# W990X.net
KiCad netlist of a schematic drawn in EAGLE
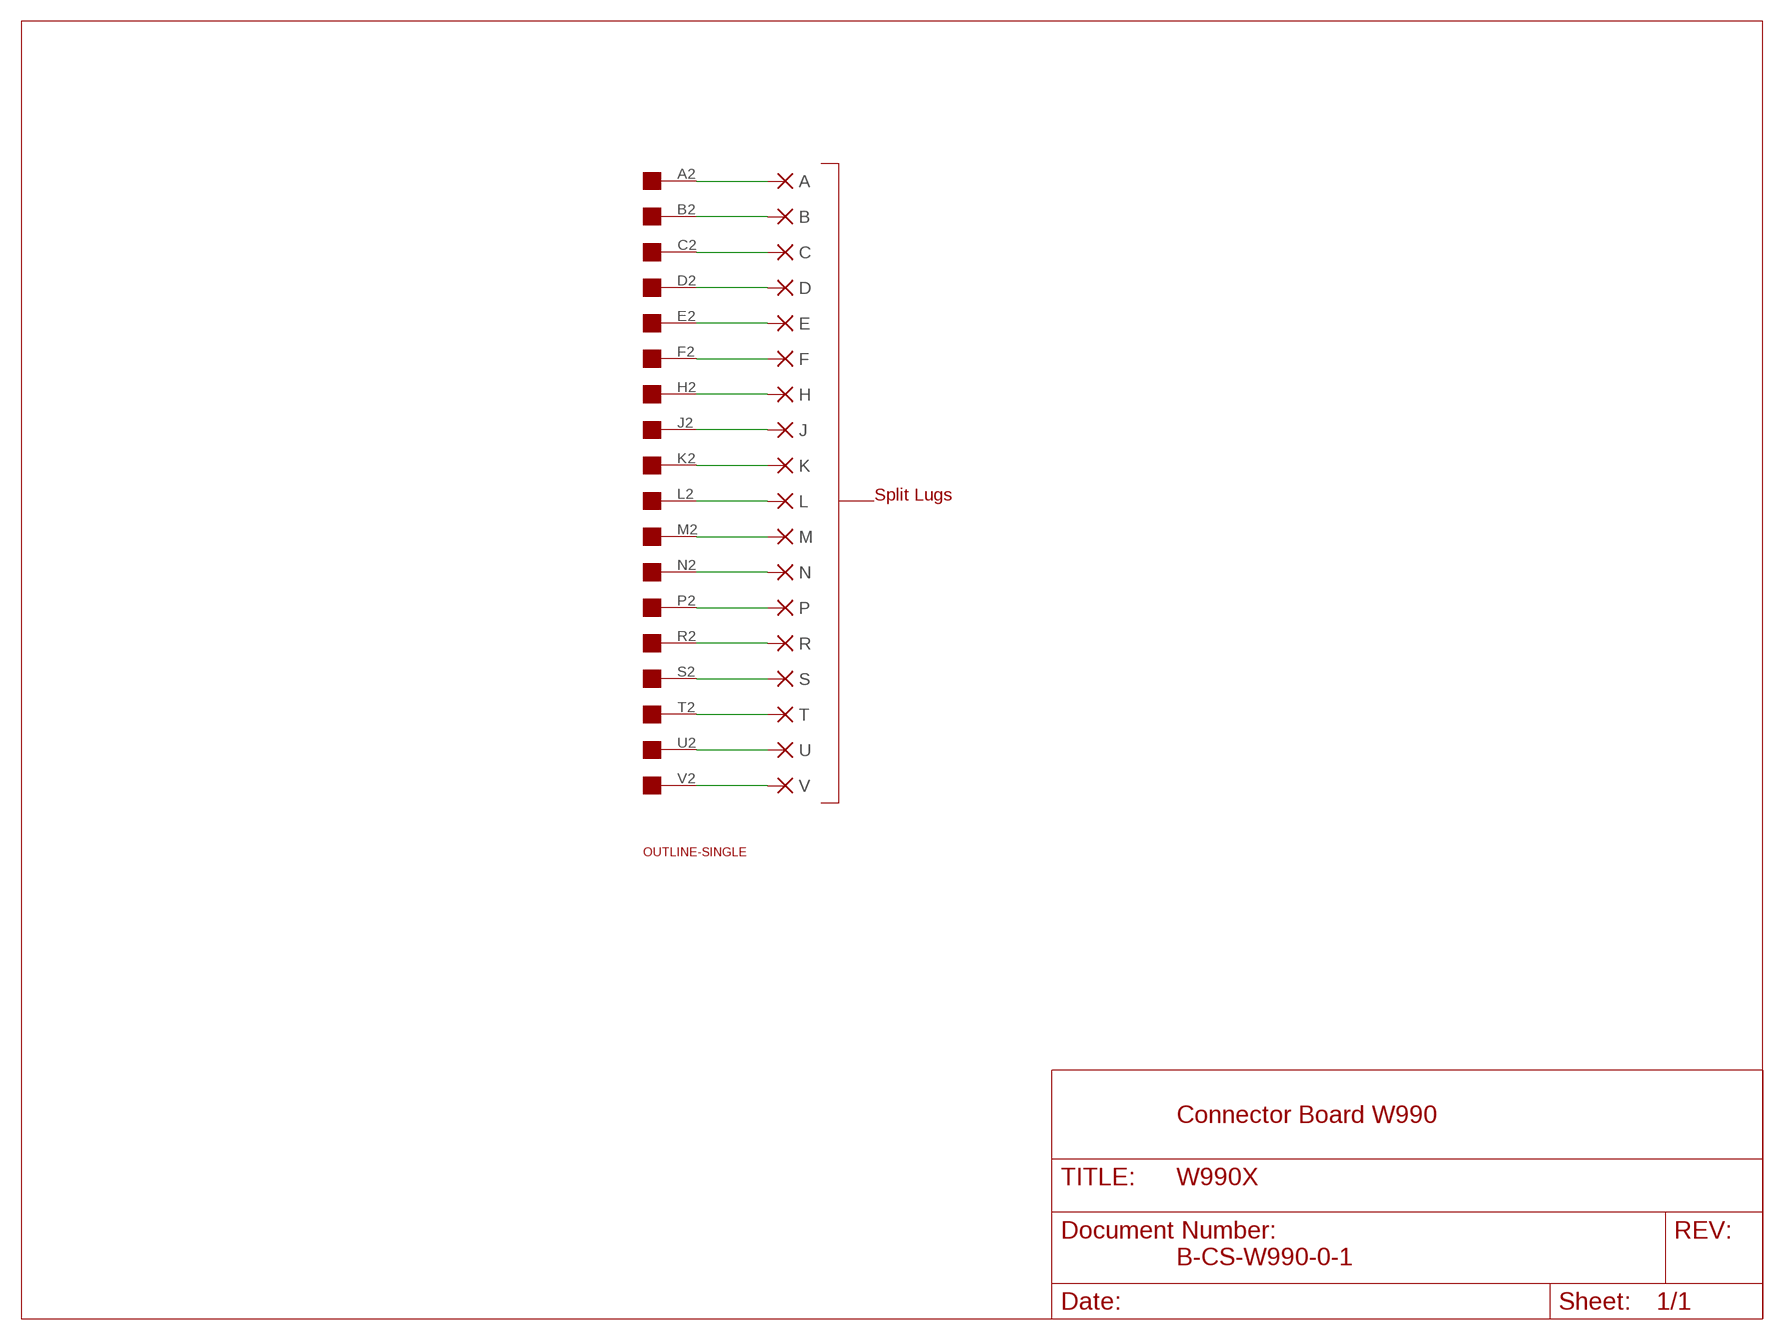
[diagram p0: schematic, sheet 1]

(export (version "E")
  (design (tool "Eeschema 10.0.6"))
  (components
    (comp (ref "A")
      (value "PAD-0465")
      (footprint "eagle-import:0465")
      (libsource (lib "eagle-import") (part "PAD-0465"))
    )
    (comp (ref "B")
      (value "PAD-0465")
      (footprint "eagle-import:0465")
      (libsource (lib "eagle-import") (part "PAD-0465"))
    )
    (comp (ref "C")
      (value "PAD-0465")
      (footprint "eagle-import:0465")
      (libsource (lib "eagle-import") (part "PAD-0465"))
    )
    (comp (ref "D")
      (value "PAD-0465")
      (footprint "eagle-import:0465")
      (libsource (lib "eagle-import") (part "PAD-0465"))
    )
    (comp (ref "E")
      (value "PAD-0465")
      (footprint "eagle-import:0465")
      (libsource (lib "eagle-import") (part "PAD-0465"))
    )
    (comp (ref "F")
      (value "PAD-0465")
      (footprint "eagle-import:0465")
      (libsource (lib "eagle-import") (part "PAD-0465"))
    )
    (comp (ref "H")
      (value "PAD-0465")
      (footprint "eagle-import:0465")
      (libsource (lib "eagle-import") (part "PAD-0465"))
    )
    (comp (ref "J")
      (value "PAD-0465")
      (footprint "eagle-import:0465")
      (libsource (lib "eagle-import") (part "PAD-0465"))
    )
    (comp (ref "K")
      (value "PAD-0465")
      (footprint "eagle-import:0465")
      (libsource (lib "eagle-import") (part "PAD-0465"))
    )
    (comp (ref "L")
      (value "PAD-0465")
      (footprint "eagle-import:0465")
      (libsource (lib "eagle-import") (part "PAD-0465"))
    )
    (comp (ref "M")
      (value "PAD-0465")
      (footprint "eagle-import:0465")
      (libsource (lib "eagle-import") (part "PAD-0465"))
    )
    (comp (ref "N")
      (value "PAD-0465")
      (footprint "eagle-import:0465")
      (libsource (lib "eagle-import") (part "PAD-0465"))
    )
    (comp (ref "P")
      (value "PAD-0465")
      (footprint "eagle-import:0465")
      (libsource (lib "eagle-import") (part "PAD-0465"))
    )
    (comp (ref "R")
      (value "PAD-0465")
      (footprint "eagle-import:0465")
      (libsource (lib "eagle-import") (part "PAD-0465"))
    )
    (comp (ref "S")
      (value "PAD-0465")
      (footprint "eagle-import:0465")
      (libsource (lib "eagle-import") (part "PAD-0465"))
    )
    (comp (ref "T")
      (value "PAD-0465")
      (footprint "eagle-import:0465")
      (libsource (lib "eagle-import") (part "PAD-0465"))
    )
    (comp (ref "U")
      (value "PAD-0465")
      (footprint "eagle-import:0465")
      (libsource (lib "eagle-import") (part "PAD-0465"))
    )
    (comp (ref "U$2")
      (value "OUTLINE-SINGLE")
      (footprint "eagle-import:SINGLE")
      (libsource (lib "eagle-import") (part "OUTLINE-SINGLE"))
    )
    (comp (ref "U$4")
      (value "EDGE-1")
      (footprint "eagle-import:EDGE-CON1")
      (libsource (lib "eagle-import") (part "EDGE-1"))
    )
    (comp (ref "V")
      (value "PAD-0465")
      (footprint "eagle-import:0465")
      (libsource (lib "eagle-import") (part "PAD-0465"))
    )
  )
  (nets
    (net (code "1") (name "Net-(A-P)") (class "Default")
      (node (ref "A") (pin "P$1") (pinfunction "P_P$1") (pintype "passive"))
      (node (ref "U$4") (pin "A2") (pinfunction "1_A2") (pintype "bidirectional"))
    )
    (net (code "2") (name "Net-(B-P)") (class "Default")
      (node (ref "B") (pin "P$1") (pinfunction "P_P$1") (pintype "passive"))
      (node (ref "U$4") (pin "B2") (pinfunction "1_B2") (pintype "bidirectional"))
    )
    (net (code "3") (name "Net-(C-P)") (class "Default")
      (node (ref "C") (pin "P$1") (pinfunction "P_P$1") (pintype "passive"))
      (node (ref "U$4") (pin "C2") (pinfunction "1_C2") (pintype "bidirectional"))
    )
    (net (code "4") (name "Net-(D-P)") (class "Default")
      (node (ref "D") (pin "P$1") (pinfunction "P_P$1") (pintype "passive"))
      (node (ref "U$4") (pin "D2") (pinfunction "1_D2") (pintype "bidirectional"))
    )
    (net (code "5") (name "Net-(E-P)") (class "Default")
      (node (ref "E") (pin "P$1") (pinfunction "P_P$1") (pintype "passive"))
      (node (ref "U$4") (pin "E2") (pinfunction "1_E2") (pintype "bidirectional"))
    )
    (net (code "6") (name "Net-(F-P)") (class "Default")
      (node (ref "F") (pin "P$1") (pinfunction "P_P$1") (pintype "passive"))
      (node (ref "U$4") (pin "F2") (pinfunction "1_F2") (pintype "bidirectional"))
    )
    (net (code "7") (name "Net-(H-P)") (class "Default")
      (node (ref "H") (pin "P$1") (pinfunction "P_P$1") (pintype "passive"))
      (node (ref "U$4") (pin "H2") (pinfunction "1_H2") (pintype "bidirectional"))
    )
    (net (code "8") (name "Net-(J-P)") (class "Default")
      (node (ref "J") (pin "P$1") (pinfunction "P_P$1") (pintype "passive"))
      (node (ref "U$4") (pin "J2") (pinfunction "1_J2") (pintype "bidirectional"))
    )
    (net (code "9") (name "Net-(K-P)") (class "Default")
      (node (ref "K") (pin "P$1") (pinfunction "P_P$1") (pintype "passive"))
      (node (ref "U$4") (pin "K2") (pinfunction "1_K2") (pintype "bidirectional"))
    )
    (net (code "10") (name "Net-(L-P)") (class "Default")
      (node (ref "L") (pin "P$1") (pinfunction "P_P$1") (pintype "passive"))
      (node (ref "U$4") (pin "L2") (pinfunction "1_L2") (pintype "bidirectional"))
    )
    (net (code "11") (name "Net-(M-P)") (class "Default")
      (node (ref "M") (pin "P$1") (pinfunction "P_P$1") (pintype "passive"))
      (node (ref "U$4") (pin "M2") (pinfunction "1_M2") (pintype "bidirectional"))
    )
    (net (code "12") (name "Net-(N-P)") (class "Default")
      (node (ref "N") (pin "P$1") (pinfunction "P_P$1") (pintype "passive"))
      (node (ref "U$4") (pin "N2") (pinfunction "1_N2") (pintype "bidirectional"))
    )
    (net (code "13") (name "Net-(P-P)") (class "Default")
      (node (ref "P") (pin "P$1") (pinfunction "P_P$1") (pintype "passive"))
      (node (ref "U$4") (pin "P2") (pinfunction "1_P2") (pintype "bidirectional"))
    )
    (net (code "14") (name "Net-(R-P)") (class "Default")
      (node (ref "R") (pin "P$1") (pinfunction "P_P$1") (pintype "passive"))
      (node (ref "U$4") (pin "R2") (pinfunction "1_R2") (pintype "bidirectional"))
    )
    (net (code "15") (name "Net-(S-P)") (class "Default")
      (node (ref "S") (pin "P$1") (pinfunction "P_P$1") (pintype "passive"))
      (node (ref "U$4") (pin "S2") (pinfunction "1_S2") (pintype "bidirectional"))
    )
    (net (code "16") (name "Net-(T-P)") (class "Default")
      (node (ref "T") (pin "P$1") (pinfunction "P_P$1") (pintype "passive"))
      (node (ref "U$4") (pin "T2") (pinfunction "1_T2") (pintype "bidirectional"))
    )
    (net (code "17") (name "Net-(U$4Q-1)") (class "Default")
      (node (ref "U") (pin "P$1") (pinfunction "P_P$1") (pintype "passive"))
      (node (ref "U$4") (pin "U2") (pinfunction "1_U2") (pintype "bidirectional"))
    )
    (net (code "18") (name "Net-(U$4R-1)") (class "Default")
      (node (ref "U$4") (pin "V2") (pinfunction "1_V2") (pintype "bidirectional"))
      (node (ref "V") (pin "P$1") (pinfunction "P_P$1") (pintype "passive"))
    )
  )
)
